# WIFI_V_1_0.net
KiCad netlist of a schematic drawn in EAGLE
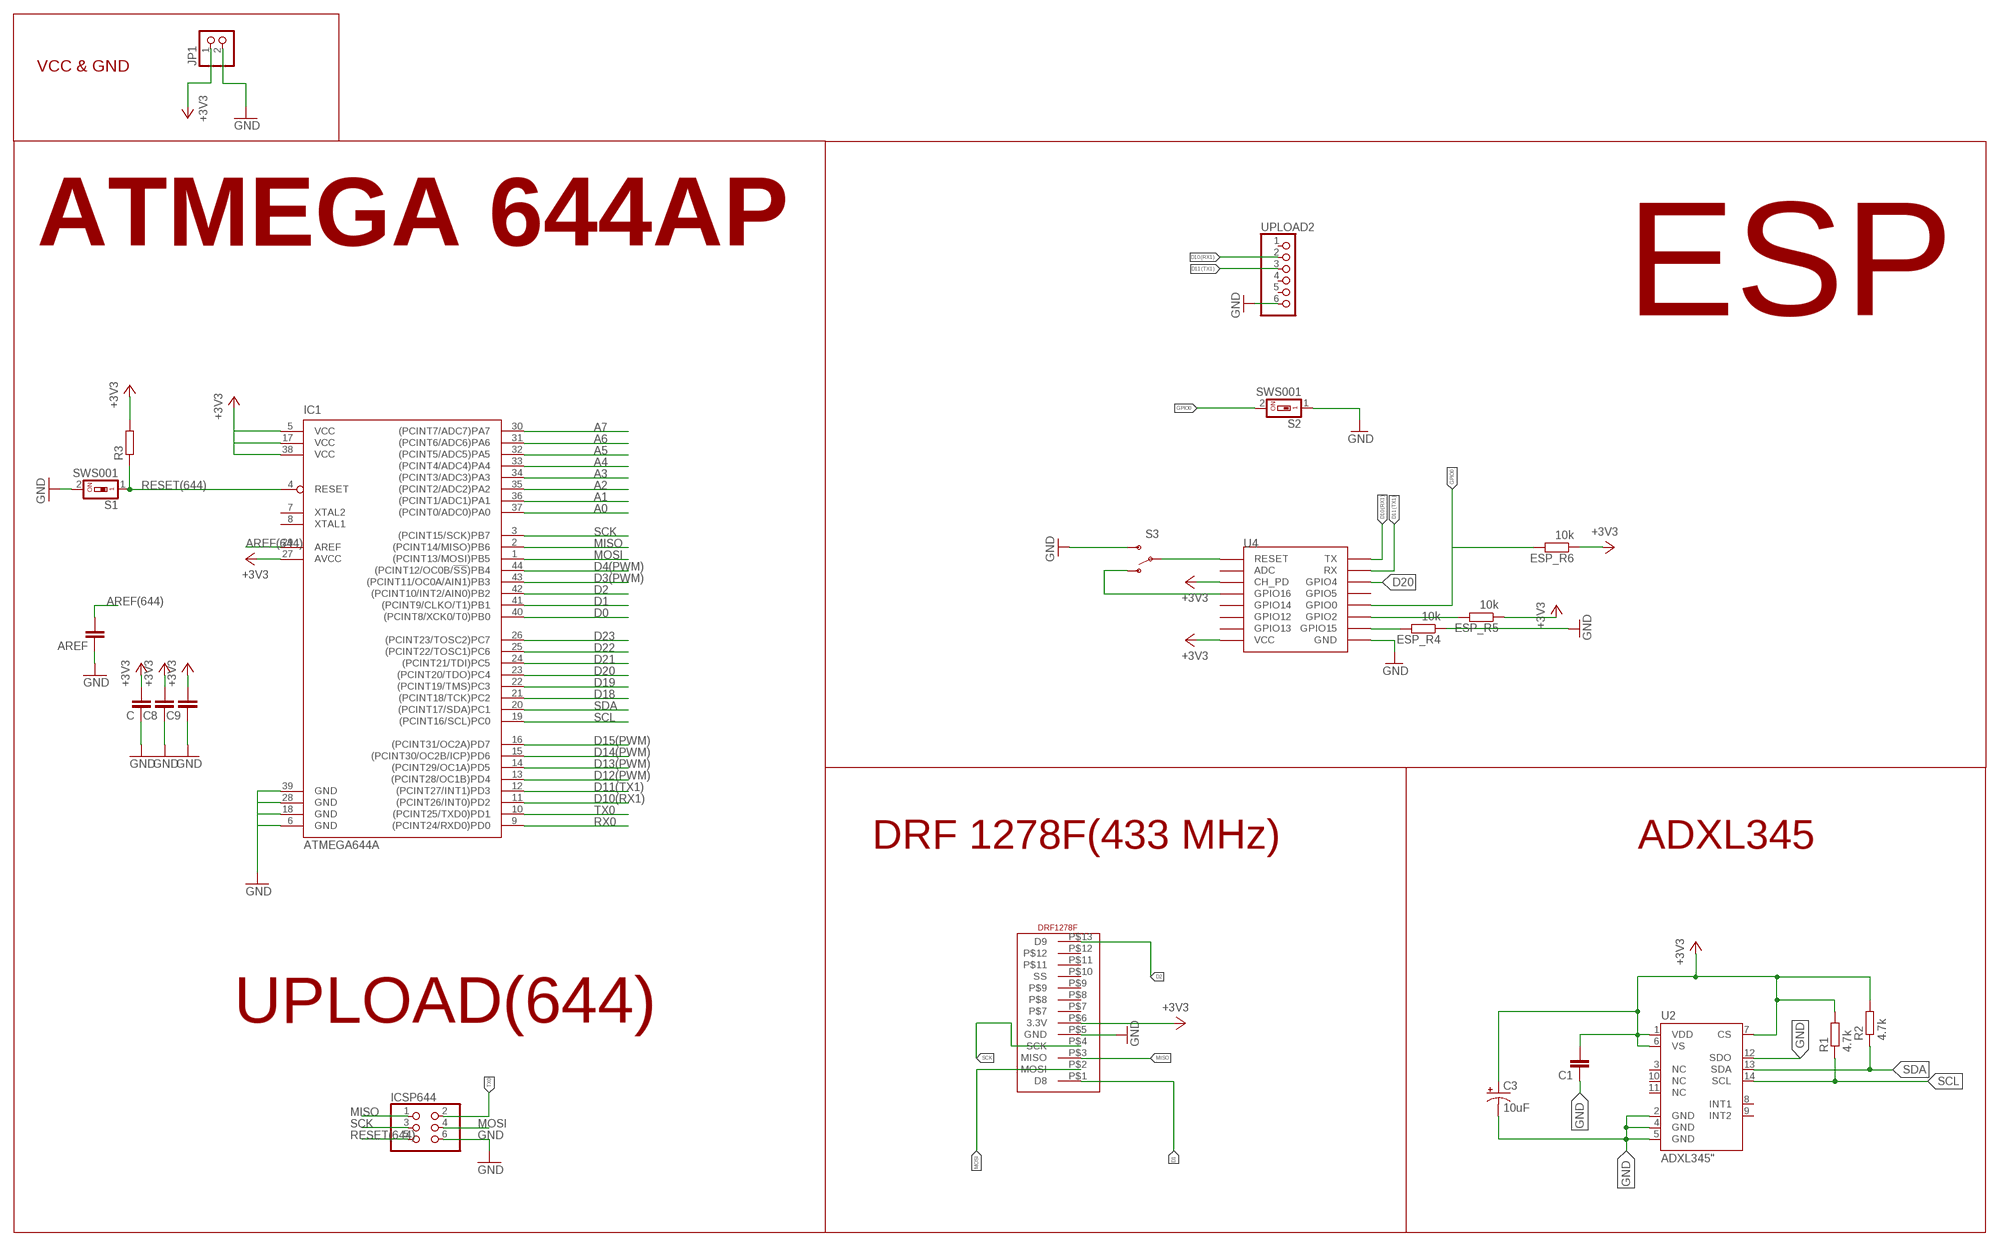
[diagram p0: schematic, sheet 1]

(export (version "E")
  (design (tool "Eeschema 10.0.6"))
  (components
    (comp (ref "AREF")
      (value "100nF")
      (footprint "eagle-import:C0805")
      (libsource (lib "eagle-import") (part "C-EUC0805"))
    )
    (comp (ref "C")
      (value "22 uF")
      (footprint "eagle-import:C0805")
      (libsource (lib "eagle-import") (part "C-EUC0805"))
    )
    (comp (ref "C1")
      (value "0.1uF")
      (footprint "eagle-import:C0805")
      (libsource (lib "eagle-import") (part "C-EUC0805"))
    )
    (comp (ref "C3")
      (value "10uF")
      (footprint "eagle-import:EIA3216")
      (libsource (lib "eagle-import") (part "CAP_POL1206"))
    )
    (comp (ref "C8")
      (value "100nF")
      (footprint "eagle-import:C0805")
      (libsource (lib "eagle-import") (part "C-EUC0805"))
    )
    (comp (ref "C9")
      (value "100nF")
      (footprint "eagle-import:C0805")
      (libsource (lib "eagle-import") (part "C-EUC0805"))
    )
    (comp (ref "ESP_R4")
      (value "10k")
      (footprint "eagle-import:R0805")
      (libsource (lib "eagle-import") (part "R-EU_R0805"))
    )
    (comp (ref "ESP_R5")
      (value "10k")
      (footprint "eagle-import:R0805")
      (libsource (lib "eagle-import") (part "R-EU_R0805"))
    )
    (comp (ref "ESP_R6")
      (value "10k")
      (footprint "eagle-import:R0805")
      (libsource (lib "eagle-import") (part "R-EU_R0805"))
    )
    (comp (ref "IC1")
      (value "ATMEGA644A")
      (footprint "eagle-import:TQFP44")
      (fields (field (name "MPN") "ATMEGA644PV-10AU"))
      (libsource (lib "eagle-import") (part "ATMEGA644A"))
    )
    (comp (ref "ICSP644")
      (value "PINHD-2X3")
      (footprint "eagle-import:2X03")
      (libsource (lib "eagle-import") (part "PINHD-2X3"))
    )
    (comp (ref "JP1")
      (value "PINHD-1X2")
      (footprint "eagle-import:1X02")
      (libsource (lib "eagle-import") (part "PINHD-1X2"))
    )
    (comp (ref "R1")
      (value "4.7k")
      (footprint "eagle-import:R0805")
      (libsource (lib "eagle-import") (part "R-EU_R0805"))
    )
    (comp (ref "R2")
      (value "4.7k")
      (footprint "eagle-import:R0805")
      (libsource (lib "eagle-import") (part "R-EU_R0805"))
    )
    (comp (ref "R3")
      (value "R-EU_R0805")
      (footprint "eagle-import:R0805")
      (libsource (lib "eagle-import") (part "R-EU_R0805"))
    )
    (comp (ref "S1")
      (value "SWS001")
      (footprint "eagle-import:SMS-001")
      (libsource (lib "eagle-import") (part "SWS001"))
    )
    (comp (ref "S2")
      (value "SWS001")
      (footprint "eagle-import:SMS-001")
      (libsource (lib "eagle-import") (part "SWS001"))
    )
    (comp (ref "S3")
      (value "SWITCH-SPDTPTH")
      (footprint "eagle-import:SWITCH-SPDT")
      (libsource (lib "eagle-import") (part "SWITCH-SPDTPTH"))
    )
    (comp (ref "U$1")
      (value "DRF1278F")
      (footprint "eagle-import:DIP13")
      (libsource (lib "eagle-import") (part "DRF1278F"))
    )
    (comp (ref "U2")
      (value "ADXL345\"")
      (footprint "eagle-import:ADXL3451_1")
      (libsource (lib "eagle-import") (part "ADXL345{dblquote}"))
    )
    (comp (ref "U4")
      (value "ESP12SMD")
      (footprint "eagle-import:ESP12-SMD")
      (libsource (lib "eagle-import") (part "ESP12SMD"))
    )
    (comp (ref "UPLOAD2")
      (value "PINHD-1X6")
      (footprint "eagle-import:1X06")
      (libsource (lib "eagle-import") (part "PINHD-1X6"))
    )
  )
  (nets
    (net (code "1") (name "+3V3") (class "Default")
      (node (ref "C") (pin "2") (pinfunction "2_2") (pintype "passive"))
      (node (ref "C1") (pin "2") (pinfunction "2_2") (pintype "passive"))
      (node (ref "C3") (pin "A") (pinfunction "+_A") (pintype "passive"))
      (node (ref "C8") (pin "2") (pinfunction "2_2") (pintype "passive"))
      (node (ref "C9") (pin "2") (pinfunction "2_2") (pintype "passive"))
      (node (ref "ESP_R5") (pin "1") (pinfunction "1_1") (pintype "passive"))
      (node (ref "ESP_R6") (pin "1") (pinfunction "1_1") (pintype "passive"))
      (node (ref "IC1") (pin "17") (pinfunction "VCC_17") (pintype "power_in"))
      (node (ref "IC1") (pin "27") (pinfunction "AVCC_27") (pintype "power_in"))
      (node (ref "IC1") (pin "38") (pinfunction "VCC_38") (pintype "power_in"))
      (node (ref "IC1") (pin "5") (pinfunction "VCC_5") (pintype "power_in"))
      (node (ref "JP1") (pin "1") (pinfunction "1_1") (pintype "passive"))
      (node (ref "R1") (pin "2") (pinfunction "2_2") (pintype "passive"))
      (node (ref "R2") (pin "2") (pinfunction "2_2") (pintype "passive"))
      (node (ref "R3") (pin "2") (pinfunction "2_2") (pintype "passive"))
      (node (ref "U$1") (pin "P$6") (pinfunction "3.3V_P$6") (pintype "bidirectional"))
      (node (ref "U2") (pin "1") (pinfunction "VDD_1") (pintype "bidirectional"))
      (node (ref "U2") (pin "6") (pinfunction "VS_6") (pintype "bidirectional"))
      (node (ref "U2") (pin "7") (pinfunction "CS_7") (pintype "bidirectional"))
      (node (ref "U4") (pin "CH_PD") (pinfunction "CH_PD_CH_PD") (pintype "bidirectional"))
      (node (ref "U4") (pin "VCC") (pinfunction "VCC_VCC") (pintype "bidirectional"))
    )
    (net (code "2") (name "/A0") (class "Default")
      (node (ref "IC1") (pin "37") (pinfunction "(PCINT0/ADC0)PA0_37") (pintype "bidirectional"))
    )
    (net (code "3") (name "/A1") (class "Default")
      (node (ref "IC1") (pin "36") (pinfunction "(PCINT1/ADC1)PA1_36") (pintype "bidirectional"))
    )
    (net (code "4") (name "/A2") (class "Default")
      (node (ref "IC1") (pin "35") (pinfunction "(PCINT2/ADC2)PA2_35") (pintype "bidirectional"))
    )
    (net (code "5") (name "/A3") (class "Default")
      (node (ref "IC1") (pin "34") (pinfunction "(PCINT3/ADC3)PA3_34") (pintype "bidirectional"))
    )
    (net (code "6") (name "/A4") (class "Default")
      (node (ref "IC1") (pin "33") (pinfunction "(PCINT4/ADC4)PA4_33") (pintype "bidirectional"))
    )
    (net (code "7") (name "/A5") (class "Default")
      (node (ref "IC1") (pin "32") (pinfunction "(PCINT5/ADC5)PA5_32") (pintype "bidirectional"))
    )
    (net (code "8") (name "/A6") (class "Default")
      (node (ref "IC1") (pin "31") (pinfunction "(PCINT6/ADC6)PA6_31") (pintype "bidirectional"))
    )
    (net (code "9") (name "/A7") (class "Default")
      (node (ref "IC1") (pin "30") (pinfunction "(PCINT7/ADC7)PA7_30") (pintype "bidirectional"))
    )
    (net (code "10") (name "/AREF(644)") (class "Default")
      (node (ref "AREF") (pin "2") (pinfunction "2_2") (pintype "passive"))
      (node (ref "IC1") (pin "29") (pinfunction "AREF_29") (pintype "passive"))
    )
    (net (code "11") (name "/D0") (class "Default")
      (node (ref "IC1") (pin "40") (pinfunction "(PCINT8/XCK0/T0)PB0_40") (pintype "bidirectional"))
    )
    (net (code "12") (name "/D3(PWM)") (class "Default")
      (node (ref "IC1") (pin "43") (pinfunction "(PCINT11/OC0A/AIN1)PB3_43") (pintype "bidirectional"))
    )
    (net (code "13") (name "/D4(PWM)") (class "Default")
      (node (ref "IC1") (pin "44") (pinfunction "(PCINT12/OC0B/~{SS})PB4_44") (pintype "bidirectional"))
    )
    (net (code "14") (name "/D12(PWM)") (class "Default")
      (node (ref "IC1") (pin "13") (pinfunction "(PCINT28/OC1B)PD4_13") (pintype "bidirectional"))
    )
    (net (code "15") (name "/D13(PWM)") (class "Default")
      (node (ref "IC1") (pin "14") (pinfunction "(PCINT29/OC1A)PD5_14") (pintype "bidirectional"))
    )
    (net (code "16") (name "/D14(PWM)") (class "Default")
      (node (ref "IC1") (pin "15") (pinfunction "(PCINT30/OC2B/ICP)PD6_15") (pintype "bidirectional"))
    )
    (net (code "17") (name "/D15(PWM)") (class "Default")
      (node (ref "IC1") (pin "16") (pinfunction "(PCINT31/OC2A)PD7_16") (pintype "bidirectional"))
    )
    (net (code "18") (name "/D18") (class "Default")
      (node (ref "IC1") (pin "21") (pinfunction "(PCINT18/TCK)PC2_21") (pintype "output"))
    )
    (net (code "19") (name "/D19") (class "Default")
      (node (ref "IC1") (pin "22") (pinfunction "(PCINT19/TMS)PC3_22") (pintype "output"))
    )
    (net (code "20") (name "/D21") (class "Default")
      (node (ref "IC1") (pin "24") (pinfunction "(PCINT21/TDI)PC5_24") (pintype "output"))
    )
    (net (code "21") (name "/D22") (class "Default")
      (node (ref "IC1") (pin "25") (pinfunction "(PCINT22/TOSC1)PC6_25") (pintype "output"))
    )
    (net (code "22") (name "/D23") (class "Default")
      (node (ref "IC1") (pin "26") (pinfunction "(PCINT23/TOSC2)PC7_26") (pintype "output"))
    )
    (net (code "23") (name "/RESET(644)") (class "Default")
      (node (ref "IC1") (pin "4") (pinfunction "RESET_4") (pintype "input"))
      (node (ref "ICSP644") (pin "5") (pinfunction "5_5") (pintype "passive"))
      (node (ref "R3") (pin "1") (pinfunction "1_1") (pintype "passive"))
      (node (ref "S1") (pin "1") (pinfunction "1_1") (pintype "passive"))
    )
    (net (code "24") (name "/RX0") (class "Default")
      (node (ref "IC1") (pin "9") (pinfunction "(PCINT24/RXD0)PD0_9") (pintype "bidirectional"))
    )
    (net (code "25") (name "D1") (class "Default")
      (node (ref "IC1") (pin "41") (pinfunction "(PCINT9/CLKO/T1)PB1_41") (pintype "bidirectional"))
      (node (ref "U$1") (pin "P$1") (pinfunction "D8_P$1") (pintype "bidirectional"))
    )
    (net (code "26") (name "D2") (class "Default")
      (node (ref "IC1") (pin "42") (pinfunction "(PCINT10/INT2/AIN0)PB2_42") (pintype "bidirectional"))
      (node (ref "U$1") (pin "P$13") (pinfunction "D9_P$13") (pintype "bidirectional"))
    )
    (net (code "27") (name "D10(RX1)") (class "Default")
      (node (ref "IC1") (pin "11") (pinfunction "(PCINT26/INT0)PD2_11") (pintype "bidirectional"))
      (node (ref "U4") (pin "TXD0") (pinfunction "TX_TXD0") (pintype "bidirectional"))
      (node (ref "UPLOAD2") (pin "2") (pinfunction "2_2") (pintype "passive"))
    )
    (net (code "28") (name "D11(TX1)") (class "Default")
      (node (ref "IC1") (pin "12") (pinfunction "(PCINT27/INT1)PD3_12") (pintype "bidirectional"))
      (node (ref "U4") (pin "RXD0") (pinfunction "RX_RXD0") (pintype "bidirectional"))
      (node (ref "UPLOAD2") (pin "3") (pinfunction "3_3") (pintype "passive"))
    )
    (net (code "29") (name "D20") (class "Default")
      (node (ref "IC1") (pin "23") (pinfunction "(PCINT20/TDO)PC4_23") (pintype "output"))
      (node (ref "U4") (pin "GPIO4") (pinfunction "GPIO4_GPIO4") (pintype "bidirectional"))
    )
    (net (code "30") (name "GND") (class "Default")
      (node (ref "AREF") (pin "1") (pinfunction "1_1") (pintype "passive"))
      (node (ref "C") (pin "1") (pinfunction "1_1") (pintype "passive"))
      (node (ref "C1") (pin "1") (pinfunction "1_1") (pintype "passive"))
      (node (ref "C3") (pin "C") (pinfunction "-_C") (pintype "passive"))
      (node (ref "C8") (pin "1") (pinfunction "1_1") (pintype "passive"))
      (node (ref "C9") (pin "1") (pinfunction "1_1") (pintype "passive"))
      (node (ref "ESP_R4") (pin "1") (pinfunction "1_1") (pintype "passive"))
      (node (ref "IC1") (pin "18") (pinfunction "GND_18") (pintype "power_in"))
      (node (ref "IC1") (pin "28") (pinfunction "GND_28") (pintype "power_in"))
      (node (ref "IC1") (pin "39") (pinfunction "GND_39") (pintype "power_in"))
      (node (ref "IC1") (pin "6") (pinfunction "GND_6") (pintype "power_in"))
      (node (ref "ICSP644") (pin "6") (pinfunction "6_6") (pintype "passive"))
      (node (ref "JP1") (pin "2") (pinfunction "2_2") (pintype "passive"))
      (node (ref "S1") (pin "2") (pinfunction "2_2") (pintype "passive"))
      (node (ref "S2") (pin "1") (pinfunction "1_1") (pintype "passive"))
      (node (ref "S3") (pin "3") (pinfunction "S_3") (pintype "passive"))
      (node (ref "U$1") (pin "P$5") (pinfunction "GND_P$5") (pintype "bidirectional"))
      (node (ref "U2") (pin "12") (pinfunction "SDO_12") (pintype "bidirectional"))
      (node (ref "U2") (pin "2") (pinfunction "GND_2") (pintype "bidirectional"))
      (node (ref "U2") (pin "4") (pinfunction "GND_4") (pintype "bidirectional"))
      (node (ref "U2") (pin "5") (pinfunction "GND_5") (pintype "bidirectional"))
      (node (ref "U4") (pin "GND") (pinfunction "GND_GND") (pintype "bidirectional"))
      (node (ref "UPLOAD2") (pin "6") (pinfunction "6_6") (pintype "passive"))
    )
    (net (code "31") (name "GPIO0") (class "Default")
      (node (ref "ESP_R6") (pin "2") (pinfunction "2_2") (pintype "passive"))
      (node (ref "S2") (pin "2") (pinfunction "2_2") (pintype "passive"))
      (node (ref "U4") (pin "GPIO0") (pinfunction "GPIO0_GPIO0") (pintype "bidirectional"))
    )
    (net (code "32") (name "MISO") (class "Default")
      (node (ref "IC1") (pin "2") (pinfunction "(PCINT14/MISO)PB6_2") (pintype "bidirectional"))
      (node (ref "ICSP644") (pin "1") (pinfunction "1_1") (pintype "passive"))
      (node (ref "U$1") (pin "P$3") (pinfunction "MISO_P$3") (pintype "bidirectional"))
    )
    (net (code "33") (name "MOSI") (class "Default")
      (node (ref "IC1") (pin "1") (pinfunction "(PCINT13/MOSI)PB5_1") (pintype "bidirectional"))
      (node (ref "ICSP644") (pin "4") (pinfunction "4_4") (pintype "passive"))
      (node (ref "U$1") (pin "P$2") (pinfunction "MOSI_P$2") (pintype "bidirectional"))
    )
    (net (code "34") (name "Net-(ESP_R4-Pad2)") (class "Default")
      (node (ref "ESP_R4") (pin "2") (pinfunction "2_2") (pintype "passive"))
      (node (ref "U4") (pin "GPIO15") (pinfunction "GPIO15_GPIO15") (pintype "bidirectional"))
    )
    (net (code "35") (name "Net-(ESP_R5-Pad2)") (class "Default")
      (node (ref "ESP_R5") (pin "2") (pinfunction "2_2") (pintype "passive"))
      (node (ref "U4") (pin "GPIO2") (pinfunction "GPIO2_GPIO2") (pintype "bidirectional"))
    )
    (net (code "36") (name "Net-(S3-O)") (class "Default")
      (node (ref "S3") (pin "1") (pinfunction "O_1") (pintype "passive"))
      (node (ref "U4") (pin "GPIO16") (pinfunction "GPIO16_GPIO16") (pintype "bidirectional"))
    )
    (net (code "37") (name "Net-(S3-P)") (class "Default")
      (node (ref "S3") (pin "2") (pinfunction "P_2") (pintype "passive"))
      (node (ref "U4") (pin "RESET") (pinfunction "RESET_RESET") (pintype "bidirectional"))
    )
    (net (code "38") (name "SCK") (class "Default")
      (node (ref "IC1") (pin "3") (pinfunction "(PCINT15/SCK)PB7_3") (pintype "bidirectional"))
      (node (ref "ICSP644") (pin "3") (pinfunction "3_3") (pintype "passive"))
      (node (ref "U$1") (pin "P$4") (pinfunction "SCK_P$4") (pintype "bidirectional"))
    )
    (net (code "39") (name "SCL") (class "Default")
      (node (ref "IC1") (pin "19") (pinfunction "(PCINT16/SCL)PC0_19") (pintype "output"))
      (node (ref "R1") (pin "1") (pinfunction "1_1") (pintype "passive"))
      (node (ref "U2") (pin "14") (pinfunction "SCL_14") (pintype "bidirectional"))
    )
    (net (code "40") (name "SDA") (class "Default")
      (node (ref "IC1") (pin "20") (pinfunction "(PCINT17/SDA)PC1_20") (pintype "output"))
      (node (ref "R2") (pin "1") (pinfunction "1_1") (pintype "passive"))
      (node (ref "U2") (pin "13") (pinfunction "SDA_13") (pintype "bidirectional"))
    )
    (net (code "41") (name "TX0") (class "Default")
      (node (ref "IC1") (pin "10") (pinfunction "(PCINT25/TXD0)PD1_10") (pintype "bidirectional"))
      (node (ref "ICSP644") (pin "2") (pinfunction "2_2") (pintype "passive"))
    )
    (net (code "42") (name "unconnected-(IC1-XTAL1-Pad8)") (class "Default")
      (node (ref "IC1") (pin "8") (pinfunction "XTAL1_8") (pintype "bidirectional"))
    )
    (net (code "43") (name "unconnected-(IC1-XTAL2-Pad7)") (class "Default")
      (node (ref "IC1") (pin "7") (pinfunction "XTAL2_7") (pintype "bidirectional"))
    )
    (net (code "44") (name "unconnected-(U$1-PadP$7)") (class "Default")
      (node (ref "U$1") (pin "P$7") (pinfunction "P$7_P$7") (pintype "bidirectional"))
    )
    (net (code "45") (name "unconnected-(U$1-PadP$8)") (class "Default")
      (node (ref "U$1") (pin "P$8") (pinfunction "P$8_P$8") (pintype "bidirectional"))
    )
    (net (code "46") (name "unconnected-(U$1-PadP$9)") (class "Default")
      (node (ref "U$1") (pin "P$9") (pinfunction "P$9_P$9") (pintype "bidirectional"))
    )
    (net (code "47") (name "unconnected-(U$1-PadP$11)") (class "Default")
      (node (ref "U$1") (pin "P$11") (pinfunction "P$11_P$11") (pintype "bidirectional"))
    )
    (net (code "48") (name "unconnected-(U$1-PadP$12)") (class "Default")
      (node (ref "U$1") (pin "P$12") (pinfunction "P$12_P$12") (pintype "bidirectional"))
    )
    (net (code "49") (name "unconnected-(U$1-SS-PadP$10)") (class "Default")
      (node (ref "U$1") (pin "P$10") (pinfunction "SS_P$10") (pintype "bidirectional"))
    )
    (net (code "50") (name "unconnected-(U2-INT1-Pad8)") (class "Default")
      (node (ref "U2") (pin "8") (pinfunction "INT1_8") (pintype "bidirectional"))
    )
    (net (code "51") (name "unconnected-(U2-INT2-Pad9)") (class "Default")
      (node (ref "U2") (pin "9") (pinfunction "INT2_9") (pintype "bidirectional"))
    )
    (net (code "52") (name "unconnected-(U2-NC-Pad3)") (class "Default")
      (node (ref "U2") (pin "3") (pinfunction "NC_3") (pintype "bidirectional"))
    )
    (net (code "53") (name "unconnected-(U2-NC-Pad10)") (class "Default")
      (node (ref "U2") (pin "10") (pinfunction "NC_10") (pintype "bidirectional"))
    )
    (net (code "54") (name "unconnected-(U2-NC-Pad11)") (class "Default")
      (node (ref "U2") (pin "11") (pinfunction "NC_11") (pintype "bidirectional"))
    )
    (net (code "55") (name "unconnected-(U4-PadADC)") (class "Default")
      (node (ref "U4") (pin "ADC") (pinfunction "ADC_ADC") (pintype "bidirectional"))
    )
    (net (code "56") (name "unconnected-(U4-PadGPIO5)") (class "Default")
      (node (ref "U4") (pin "GPIO5") (pinfunction "GPIO5_GPIO5") (pintype "bidirectional"))
    )
    (net (code "57") (name "unconnected-(U4-PadGPIO12)") (class "Default")
      (node (ref "U4") (pin "GPIO12") (pinfunction "GPIO12_GPIO12") (pintype "bidirectional"))
    )
    (net (code "58") (name "unconnected-(U4-PadGPIO13)") (class "Default")
      (node (ref "U4") (pin "GPIO13") (pinfunction "GPIO13_GPIO13") (pintype "bidirectional"))
    )
    (net (code "59") (name "unconnected-(U4-PadGPIO14)") (class "Default")
      (node (ref "U4") (pin "GPIO14") (pinfunction "GPIO14_GPIO14") (pintype "bidirectional"))
    )
    (net (code "60") (name "unconnected-(UPLOAD2-Pad1)") (class "Default")
      (node (ref "UPLOAD2") (pin "1") (pinfunction "1_1") (pintype "passive"))
    )
    (net (code "61") (name "unconnected-(UPLOAD2-Pad4)") (class "Default")
      (node (ref "UPLOAD2") (pin "4") (pinfunction "4_4") (pintype "passive"))
    )
    (net (code "62") (name "unconnected-(UPLOAD2-Pad5)") (class "Default")
      (node (ref "UPLOAD2") (pin "5") (pinfunction "5_5") (pintype "passive"))
    )
  )
)
